# Phase_Detector.net
KiCad netlist of a schematic drawn in Altium Designer
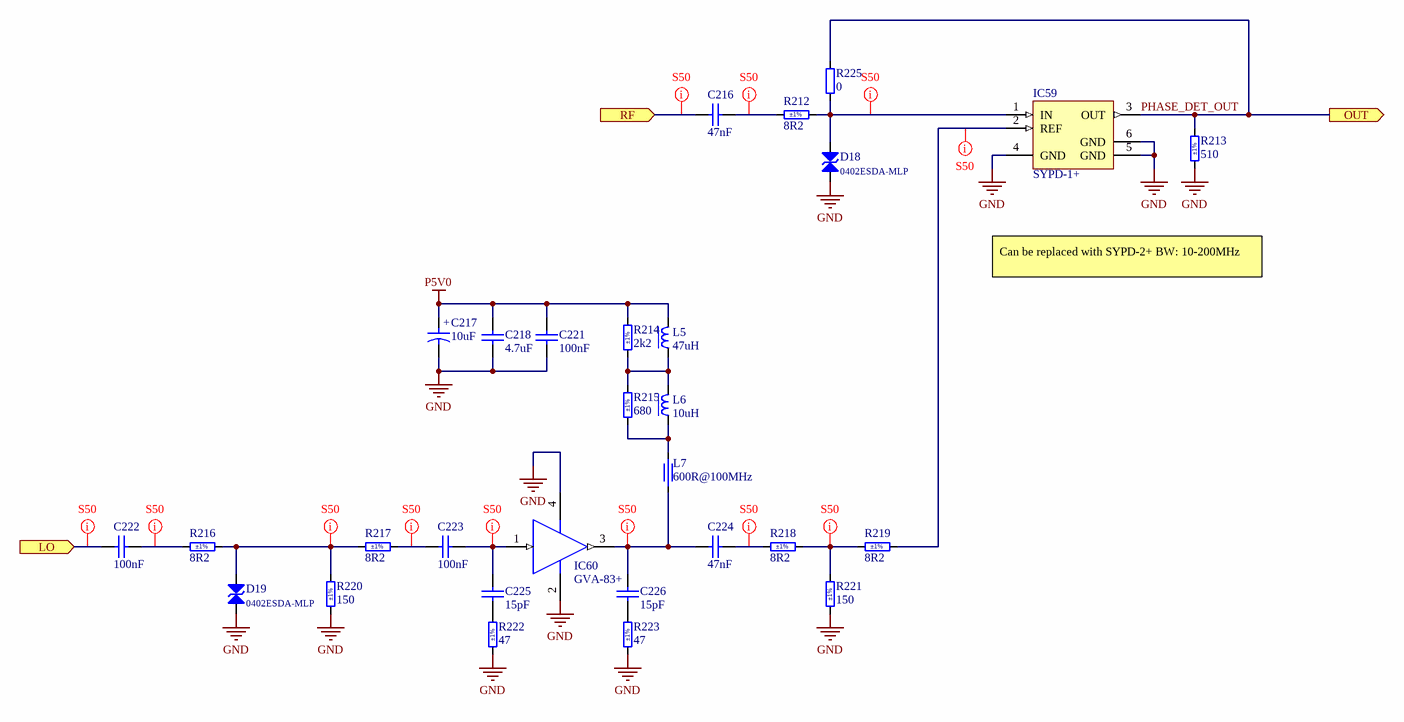
[diagram p0: Phase_Detector.SchDoc]

(export (version "E")
  (design (tool "Eeschema 10.0.6"))
  (components
    (comp (ref "C216")
      (value "47nF")
      (footprint "CAPC1005X55N")
      (description "Non-polarised capacitor")
      (fields
        (field (name "PART NUMBER") "CC0402_47NF_25V_10%_X7R")
        (field (name "VOLTAGE") "25V")
        (field (name "AUTHOR") "CERN DEM JLC")
      )
      (libsource (lib "Capacitors") (part "Capacitor - non polarized"))
    )
    (comp (ref "C217")
      (value "10uF")
      (footprint "CAPMP3216X180N")
      (description "Polarised capacitor")
      (fields
        (field (name "PART NUMBER") "CTE3216-18_10UF_10V_10%_LESR1800")
        (field (name "VOLTAGE") "10V")
        (field (name "AUTHOR") "CERN DEM JLC")
      )
      (libsource (lib "Capacitors") (part "Capacitor - polarized"))
    )
    (comp (ref "C218")
      (value "4.7uF")
      (footprint "CAPC1608X90N")
      (description "Non-polarised capacitor")
      (fields
        (field (name "PART NUMBER") "CC0603_4.7UF_25V_10%_X5R")
        (field (name "VOLTAGE") "25V")
        (field (name "AUTHOR") "CERN DEM JLC")
      )
      (libsource (lib "Capacitors") (part "Capacitor - non polarized"))
    )
    (comp (ref "C221")
      (value "100nF")
      (footprint "CAPC1005X55N")
      (description "Non-polarised capacitor")
      (fields
        (field (name "PART NUMBER") "CC0402_100NF_50V_10%_X7R")
        (field (name "VOLTAGE") "50V")
        (field (name "AUTHOR") "CERN DEM MR")
      )
      (libsource (lib "Capacitors") (part "Capacitor - non polarized"))
    )
    (comp (ref "C222")
      (value "100nF")
      (footprint "CAPC1005X55N")
      (description "Non-polarised capacitor")
      (fields
        (field (name "PART NUMBER") "CC0402_100NF_50V_10%_X7R")
        (field (name "VOLTAGE") "50V")
        (field (name "AUTHOR") "CERN DEM MR")
      )
      (libsource (lib "Capacitors") (part "Capacitor - non polarized"))
    )
    (comp (ref "C223")
      (value "100nF")
      (footprint "CAPC1005X55N")
      (description "Non-polarised capacitor")
      (fields
        (field (name "PART NUMBER") "CC0402_100NF_50V_10%_X7R")
        (field (name "VOLTAGE") "50V")
        (field (name "AUTHOR") "CERN DEM MR")
      )
      (libsource (lib "Capacitors") (part "Capacitor - non polarized"))
    )
    (comp (ref "C224")
      (value "47nF")
      (footprint "CAPC1005X55N")
      (description "Non-polarised capacitor")
      (fields
        (field (name "PART NUMBER") "CC0402_47NF_25V_10%_X7R")
        (field (name "VOLTAGE") "25V")
        (field (name "AUTHOR") "CERN DEM JLC")
      )
      (libsource (lib "Capacitors") (part "Capacitor - non polarized"))
    )
    (comp (ref "C225")
      (value "15pF")
      (footprint "CAPC1005X55N")
      (description "Non-polarised capacitor")
      (fields
        (field (name "PART NUMBER") "CC0402_15PF_50V_5%_C0G")
        (field (name "VOLTAGE") "50V")
        (field (name "AUTHOR") "CERN DEM JLC")
      )
      (libsource (lib "Capacitors") (part "Capacitor - non polarized"))
    )
    (comp (ref "C226")
      (value "15pF")
      (footprint "CAPC1005X55N")
      (description "Non-polarised capacitor")
      (fields
        (field (name "PART NUMBER") "CC0402_15PF_50V_5%_C0G")
        (field (name "VOLTAGE") "50V")
        (field (name "AUTHOR") "CERN DEM JLC")
      )
      (libsource (lib "Capacitors") (part "Capacitor - non polarized"))
    )
    (comp (ref "D18")
      (value "0402ESDA-MLP")
      (footprint "EATON_0402ESDA-MLP")
      (description "Transient Voltage Suppressor Diode (Bi-Directional)")
      (fields
        (field (name "VOLTAGE") "8kV")
        (field (name "MANUFACTURER") "EATON")
        (field (name "AUTHOR") "CERN DEM MR")
      )
      (libsource (lib "ICs And Semiconductors") (part "Diode TVS Bi-Directional"))
    )
    (comp (ref "D19")
      (value "0402ESDA-MLP")
      (footprint "EATON_0402ESDA-MLP")
      (description "Transient Voltage Suppressor Diode (Bi-Directional)")
      (fields
        (field (name "VOLTAGE") "8kV")
        (field (name "MANUFACTURER") "EATON")
        (field (name "AUTHOR") "CERN DEM MR")
      )
      (libsource (lib "ICs And Semiconductors") (part "Diode TVS Bi-Directional"))
    )
    (comp (ref "IC59")
      (value "SYPD-1+")
      (footprint "MINI-CIRCUITS_TTT167")
      (description "50 Ohm, 1 to 100MHz, High Output, Phase Detector")
      (fields
        (field (name "MANUFACTURER") "MINI-CIRCUITS")
        (field (name "MANUFACTURER PART NUMBER") "SYPD-1")
        (field (name "AUTHOR") "CERN DEM BC")
      )
      (libsource (lib "ICs And Semiconductors") (part "SYPD-1+"))
    )
    (comp (ref "IC60")
      (value "GVA-83+")
      (footprint "MINI-CIRCUITS_DF782")
      (description "Monolithic Amplifier DC-7 GHz")
      (fields (field (name "MANUFACTURER") "Mini-Circuits"))
      (libsource (lib "mb") (part "GVA-83+"))
    )
    (comp (ref "L5")
      (value "47uH")
      (footprint "IND_MURATA_LQH32C")
      (description "Inductor With Core")
      (fields
        (field (name "PART NUMBER") "IND_47UH_10%_MURATA_LQH32CN470K23L")
        (field (name "POWER") "170mA")
        (field (name "AUTHOR") "CERN DEM JLC")
      )
      (libsource (lib "Inductors & Transformers") (part "Inductor With Magnetic core"))
    )
    (comp (ref "L6")
      (value "10uH")
      (footprint "IND_MURATA_LQH32C")
      (description "Inductor With Core")
      (fields
        (field (name "PART NUMBER") "IND_10UH_10%_MURATA_LQH32CN100K33L")
        (field (name "POWER") "450mA")
        (field (name "AUTHOR") "CERN DEM JLC")
      )
      (libsource (lib "Inductors & Transformers") (part "Inductor With Magnetic core"))
    )
    (comp (ref "L7")
      (value "600R@100MHz")
      (footprint "INDC1608X95N")
      (fields
        (field (name "PART NUMBER") "IND0603_MURATA_BLM18BD601SN1D")
        (field (name "POWER") "200mA")
        (field (name "TOLERANCE") "±25%")
        (field (name "AUTHOR") "CERN DEM JLC")
      )
      (libsource (lib "Inductors & Transformers") (part "Ferrite Bead"))
    )
    (comp (ref "R212")
      (value "8R2")
      (footprint "RESC2012X60N")
      (description "Resistor - 1%")
      (fields
        (field (name "TOLERANCE") "±1%")
        (field (name "PART NUMBER") "R0805_8R2_1%_0.125W_200PPM")
        (field (name "POWER") "0.125W")
        (field (name "AUTHOR") "CERN DEM JLC")
      )
      (libsource (lib "Resistors") (part "Resistor - 1%"))
    )
    (comp (ref "R213")
      (value "510")
      (footprint "RESC1005X40N")
      (description "Resistor - 1%")
      (fields
        (field (name "TOLERANCE") "±1%")
        (field (name "PART NUMBER") "R0402_510R_1%_0.0625W_100PPM")
        (field (name "POWER") "0.0625W")
        (field (name "AUTHOR") "CERN DEM JLC")
      )
      (libsource (lib "Resistors") (part "Resistor - 1%"))
    )
    (comp (ref "R214")
      (value "2k2")
      (footprint "RESC1005X40N")
      (description "Resistor - 1%")
      (fields
        (field (name "TOLERANCE") "±1%")
        (field (name "PART NUMBER") "R0402_2K2_1%_0.0625W_100PPM")
        (field (name "POWER") "0.0625W")
        (field (name "AUTHOR") "CERN DEM JLC")
      )
      (libsource (lib "Resistors") (part "Resistor - 1%"))
    )
    (comp (ref "R215")
      (value "680")
      (footprint "RESC1005X40N")
      (description "Resistor - 1%")
      (fields
        (field (name "TOLERANCE") "±1%")
        (field (name "PART NUMBER") "R0402_680R_1%_0.0625W_100PPM")
        (field (name "POWER") "0.0625W")
        (field (name "AUTHOR") "CERN DEM JLC")
      )
      (libsource (lib "Resistors") (part "Resistor - 1%"))
    )
    (comp (ref "R216")
      (value "8R2")
      (footprint "RESC2012X60N")
      (description "Resistor - 1%")
      (fields
        (field (name "TOLERANCE") "±1%")
        (field (name "PART NUMBER") "R0805_8R2_1%_0.125W_200PPM")
        (field (name "POWER") "0.125W")
        (field (name "AUTHOR") "CERN DEM JLC")
      )
      (libsource (lib "Resistors") (part "Resistor - 1%"))
    )
    (comp (ref "R217")
      (value "8R2")
      (footprint "RESC2012X60N")
      (description "Resistor - 1%")
      (fields
        (field (name "TOLERANCE") "±1%")
        (field (name "PART NUMBER") "R0805_8R2_1%_0.125W_200PPM")
        (field (name "POWER") "0.125W")
        (field (name "AUTHOR") "CERN DEM JLC")
      )
      (libsource (lib "Resistors") (part "Resistor - 1%"))
    )
    (comp (ref "R218")
      (value "8R2")
      (footprint "RESC2012X60N")
      (description "Resistor - 1%")
      (fields
        (field (name "TOLERANCE") "±1%")
        (field (name "PART NUMBER") "R0805_8R2_1%_0.125W_200PPM")
        (field (name "POWER") "0.125W")
        (field (name "AUTHOR") "CERN DEM JLC")
      )
      (libsource (lib "Resistors") (part "Resistor - 1%"))
    )
    (comp (ref "R219")
      (value "8R2")
      (footprint "RESC2012X60N")
      (description "Resistor - 1%")
      (fields
        (field (name "TOLERANCE") "±1%")
        (field (name "PART NUMBER") "R0805_8R2_1%_0.125W_200PPM")
        (field (name "POWER") "0.125W")
        (field (name "AUTHOR") "CERN DEM JLC")
      )
      (libsource (lib "Resistors") (part "Resistor - 1%"))
    )
    (comp (ref "R220")
      (value "150")
      (footprint "RESC2012X60N")
      (description "Resistor - 1%")
      (fields
        (field (name "TOLERANCE") "±1%")
        (field (name "PART NUMBER") "R0805_150R_1%_0.125W_100PPM")
        (field (name "POWER") "0.125W")
        (field (name "AUTHOR") "CERN DEM JLC")
      )
      (libsource (lib "Resistors") (part "Resistor - 1%"))
    )
    (comp (ref "R221")
      (value "150")
      (footprint "RESC2012X60N")
      (description "Resistor - 1%")
      (fields
        (field (name "TOLERANCE") "±1%")
        (field (name "PART NUMBER") "R0805_150R_1%_0.125W_100PPM")
        (field (name "POWER") "0.125W")
        (field (name "AUTHOR") "CERN DEM JLC")
      )
      (libsource (lib "Resistors") (part "Resistor - 1%"))
    )
    (comp (ref "R222")
      (value "47")
      (footprint "RESC1005X40N")
      (description "Resistor - 1%")
      (fields
        (field (name "TOLERANCE") "±1%")
        (field (name "PART NUMBER") "R0402_47R_1%_0.0625W_100PPM")
        (field (name "POWER") "0.0625W")
        (field (name "AUTHOR") "CERN DEM JLC")
      )
      (libsource (lib "Resistors") (part "Resistor - 1%"))
    )
    (comp (ref "R223")
      (value "47")
      (footprint "RESC1005X40N")
      (description "Resistor - 1%")
      (fields
        (field (name "TOLERANCE") "±1%")
        (field (name "PART NUMBER") "R0402_47R_1%_0.0625W_100PPM")
        (field (name "POWER") "0.0625W")
        (field (name "AUTHOR") "CERN DEM JLC")
      )
      (libsource (lib "Resistors") (part "Resistor - 1%"))
    )
    (comp (ref "R225")
      (value "0")
      (footprint "RESC1005X40N")
      (description "Resistor")
      (fields
        (field (name "PART NUMBER") "R0402_0R_JUMPER")
        (field (name "MANUFACTURER") "GENERIC")
        (field (name "AUTHOR") "CERN DEM JLC")
      )
      (libsource (lib "Resistors") (part "Resistor"))
    )
  )
  (nets
    (net (code "1") (name "/LO") (class "Default")
      (node (ref "C222") (pin "2") (pinfunction "2_2") (pintype "passive"))
    )
    (net (code "2") (name "/PHASE_DET_OUT") (class "Default")
      (node (ref "IC59") (pin "3") (pinfunction "OUT_3") (pintype "output"))
      (node (ref "R213") (pin "2") (pinfunction "2_2") (pintype "passive"))
      (node (ref "R225") (pin "2") (pinfunction "2_2") (pintype "passive"))
    )
    (net (code "3") (name "/RF") (class "Default")
      (node (ref "C216") (pin "1") (pinfunction "1_1") (pintype "passive"))
    )
    (net (code "4") (name "GND") (class "Default")
      (node (ref "C217") (pin "2") (pinfunction "2_2") (pintype "passive"))
      (node (ref "C218") (pin "1") (pinfunction "1_1") (pintype "passive"))
      (node (ref "C221") (pin "2") (pinfunction "2_2") (pintype "passive"))
      (node (ref "D18") (pin "1") (pinfunction "1_1") (pintype "passive"))
      (node (ref "D19") (pin "1") (pinfunction "1_1") (pintype "passive"))
      (node (ref "IC59") (pin "4") (pinfunction "GND_4") (pintype "power_in"))
      (node (ref "IC59") (pin "5") (pinfunction "GND_5") (pintype "power_in"))
      (node (ref "IC59") (pin "6") (pinfunction "GND_6") (pintype "power_in"))
      (node (ref "IC60") (pin "2") (pinfunction "GND_2") (pintype "power_in"))
      (node (ref "IC60") (pin "4") (pinfunction "GND_4") (pintype "power_in"))
      (node (ref "R213") (pin "1") (pinfunction "1_1") (pintype "passive"))
      (node (ref "R220") (pin "1") (pinfunction "1_1") (pintype "passive"))
      (node (ref "R221") (pin "1") (pinfunction "1_1") (pintype "passive"))
      (node (ref "R222") (pin "1") (pinfunction "1_1") (pintype "passive"))
      (node (ref "R223") (pin "1") (pinfunction "1_1") (pintype "passive"))
    )
    (net (code "5") (name "Net-(C216-Pad2)") (class "Default")
      (node (ref "C216") (pin "2") (pinfunction "2_2") (pintype "passive"))
      (node (ref "R212") (pin "1") (pinfunction "1_1") (pintype "passive"))
    )
    (net (code "6") (name "Net-(C222-Pad1)") (class "Default")
      (node (ref "C222") (pin "1") (pinfunction "1_1") (pintype "passive"))
      (node (ref "R216") (pin "1") (pinfunction "1_1") (pintype "passive"))
    )
    (net (code "7") (name "Net-(C223-Pad2)") (class "Default")
      (node (ref "C223") (pin "2") (pinfunction "2_2") (pintype "passive"))
      (node (ref "R217") (pin "2") (pinfunction "2_2") (pintype "passive"))
    )
    (net (code "8") (name "Net-(C224-Pad2)") (class "Default")
      (node (ref "C224") (pin "2") (pinfunction "2_2") (pintype "passive"))
      (node (ref "R218") (pin "1") (pinfunction "1_1") (pintype "passive"))
    )
    (net (code "9") (name "Net-(C225-Pad1)") (class "Default")
      (node (ref "C225") (pin "1") (pinfunction "1_1") (pintype "passive"))
      (node (ref "R222") (pin "2") (pinfunction "2_2") (pintype "passive"))
    )
    (net (code "10") (name "Net-(C226-Pad1)") (class "Default")
      (node (ref "C226") (pin "1") (pinfunction "1_1") (pintype "passive"))
      (node (ref "R223") (pin "2") (pinfunction "2_2") (pintype "passive"))
    )
    (net (code "11") (name "Net-(D19-Pad2)") (class "Default")
      (node (ref "D19") (pin "2") (pinfunction "2_2") (pintype "passive"))
      (node (ref "R216") (pin "2") (pinfunction "2_2") (pintype "passive"))
      (node (ref "R217") (pin "1") (pinfunction "1_1") (pintype "passive"))
      (node (ref "R220") (pin "2") (pinfunction "2_2") (pintype "passive"))
    )
    (net (code "12") (name "Net-(IC59-IN)") (class "Default")
      (node (ref "D18") (pin "2") (pinfunction "2_2") (pintype "passive"))
      (node (ref "IC59") (pin "1") (pinfunction "IN_1") (pintype "input"))
      (node (ref "R212") (pin "2") (pinfunction "2_2") (pintype "passive"))
      (node (ref "R225") (pin "1") (pinfunction "1_1") (pintype "passive"))
    )
    (net (code "13") (name "Net-(IC59-REF)") (class "Default")
      (node (ref "IC59") (pin "2") (pinfunction "REF_2") (pintype "input"))
      (node (ref "R219") (pin "2") (pinfunction "2_2") (pintype "passive"))
    )
    (net (code "14") (name "Net-(IC60-RF_IN)") (class "Default")
      (node (ref "C223") (pin "1") (pinfunction "1_1") (pintype "passive"))
      (node (ref "C225") (pin "2") (pinfunction "2_2") (pintype "passive"))
      (node (ref "IC60") (pin "1") (pinfunction "RF_IN_1") (pintype "input"))
    )
    (net (code "15") (name "Net-(IC60-RF_OUT)") (class "Default")
      (node (ref "C224") (pin "1") (pinfunction "1_1") (pintype "passive"))
      (node (ref "C226") (pin "2") (pinfunction "2_2") (pintype "passive"))
      (node (ref "IC60") (pin "3") (pinfunction "RF_OUT_3") (pintype "output"))
      (node (ref "L7") (pin "1") (pinfunction "1_1") (pintype "passive"))
    )
    (net (code "16") (name "Net-(L5-Pad1)") (class "Default")
      (node (ref "L5") (pin "1") (pinfunction "1_1") (pintype "passive"))
      (node (ref "L6") (pin "2") (pinfunction "2_2") (pintype "passive"))
      (node (ref "R214") (pin "1") (pinfunction "1_1") (pintype "passive"))
      (node (ref "R215") (pin "2") (pinfunction "2_2") (pintype "passive"))
    )
    (net (code "17") (name "Net-(L6-Pad1)") (class "Default")
      (node (ref "L6") (pin "1") (pinfunction "1_1") (pintype "passive"))
      (node (ref "L7") (pin "2") (pinfunction "2_2") (pintype "passive"))
      (node (ref "R215") (pin "1") (pinfunction "1_1") (pintype "passive"))
    )
    (net (code "18") (name "Net-(R218-Pad2)") (class "Default")
      (node (ref "R218") (pin "2") (pinfunction "2_2") (pintype "passive"))
      (node (ref "R219") (pin "1") (pinfunction "1_1") (pintype "passive"))
      (node (ref "R221") (pin "2") (pinfunction "2_2") (pintype "passive"))
    )
    (net (code "19") (name "P5V0") (class "Default")
      (node (ref "C217") (pin "1") (pinfunction "1_1") (pintype "passive"))
      (node (ref "C218") (pin "2") (pinfunction "2_2") (pintype "passive"))
      (node (ref "C221") (pin "1") (pinfunction "1_1") (pintype "passive"))
      (node (ref "L5") (pin "2") (pinfunction "2_2") (pintype "passive"))
      (node (ref "R214") (pin "2") (pinfunction "2_2") (pintype "passive"))
    )
  )
)
